# power.net
KiCad netlist of a schematic drawn in Altium Designer
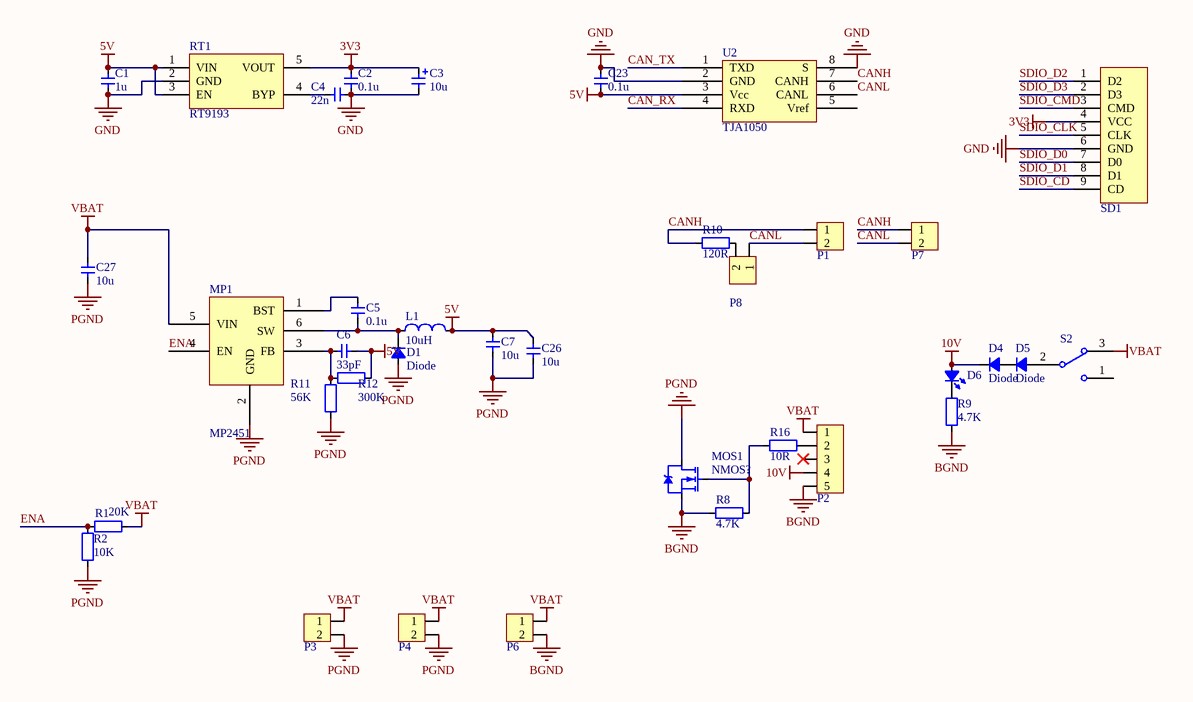
[diagram p0: power.SchDoc]

(export (version "E")
  (design (tool "Eeschema 10.0.6"))
  (components
    (comp (ref "C1")
      (value "1u")
      (footprint "PCB_PassiveCap:CAP_0603")
      (description "Capacitor")
      (fields (field (name "Comment") "Cap_0603"))
      (libsource (lib "SCH_Passive") (part "Cap_0603"))
    )
    (comp (ref "C2")
      (value "0.1u")
      (footprint "PCB_PassiveCap:CAP_0603")
      (description "Capacitor")
      (fields (field (name "Comment") "Cap_0603"))
      (libsource (lib "SCH_Passive") (part "Cap_0603"))
    )
    (comp (ref "C3")
      (value "10u")
      (footprint "PCB_PassiveCap:CAP_TAN_P0805")
      (description "Capacitor")
      (fields (field (name "Comment") "Cap_Tan_0805"))
      (libsource (lib "SCH_Passive") (part "Cap_Tan_0805"))
    )
    (comp (ref "C4")
      (value "22n")
      (footprint "PCB_PassiveCap:CAP_0603")
      (description "Capacitor")
      (fields (field (name "Comment") "Cap_0603"))
      (libsource (lib "SCH_Passive") (part "Cap_0603"))
    )
    (comp (ref "C5")
      (value "0.1u")
      (footprint "PCB_PassiveCap:CAP_0603")
      (description "Capacitor")
      (fields (field (name "Comment") "Cap_0603"))
      (libsource (lib "SCH_Passive") (part "Cap_0603"))
    )
    (comp (ref "C6")
      (value "33pF")
      (footprint "PCB_PassiveCap:CAP_0603")
      (description "Capacitor")
      (fields (field (name "Comment") "Cap_0603"))
      (libsource (lib "SCH_Passive") (part "Cap_0603"))
    )
    (comp (ref "C7")
      (value "10u")
      (footprint "PCB_PassiveCap:CAP_0805")
      (description "Capacitor")
      (fields (field (name "Comment") "Cap_0805"))
      (libsource (lib "SCH_Passive") (part "Cap_0805"))
    )
    (comp (ref "C23")
      (value "0.1u")
      (footprint "PCB_PassiveCap:CAP_0603")
      (description "Capacitor")
      (fields (field (name "Comment") "Cap_0603"))
      (libsource (lib "SCH_Passive") (part "Cap_0603"))
    )
    (comp (ref "C26")
      (value "10u")
      (footprint "PCB_PassiveCap:CAP_0805")
      (description "Capacitor")
      (fields (field (name "Comment") "Cap_0805"))
      (libsource (lib "SCH_Passive") (part "Cap_0805"))
    )
    (comp (ref "C27")
      (value "10u")
      (footprint "PCB_PassiveCap:CAP_0805")
      (description "Capacitor")
      (fields (field (name "Comment") "Cap_0805"))
      (libsource (lib "SCH_Passive") (part "Cap_0805"))
    )
    (comp (ref "D1") (value "Diode") (footprint "LED_0805_RED") (libsource (lib "SCH_Active") (part "Diode")))
    (comp (ref "D4") (value "Diode") (footprint "LED_0805_RED") (libsource (lib "SCH_Active") (part "Diode")))
    (comp (ref "D5") (value "Diode") (footprint "LED_0805_RED") (libsource (lib "SCH_Active") (part "Diode")))
    (comp (ref "D6")
      (value "LED_0805")
      (footprint "PCB_ActiveLED:LED_0805_RED")
      (description "LED")
      (libsource (lib "SCH_Active") (part "LED_0805"))
    )
    (comp (ref "L1")
      (value "10uH")
      (footprint "IND_CD52")
      (description "Inductor")
      (fields (field (name "Comment") "Ind_CD32"))
      (libsource (lib "SCH_Passive") (part "Ind_CD32"))
    )
    (comp (ref "MOS1")
      (value "NMOS?")
      (footprint "PCB_IntegratedCircuit:TO-252AA")
      (description "MOSFET")
      (fields (field (name "Comment") "MOSFET_N"))
      (libsource (lib "SCH_Active") (part "MOSFET_N"))
    )
    (comp (ref "MP1")
      (value "MP2451")
      (footprint "SOT23-6")
      (libsource (lib "SCH_IntegratedCircuit") (part "MP2451"))
    )
    (comp (ref "P1")
      (value "HDR1x2_2.54")
      (footprint "PCB_ConnectorHDR:HDR1X2_2.54_90")
      (description "Header")
      (libsource (lib "") (part "HDR1x2_2.54_1"))
    )
    (comp (ref "P2")
      (value "HDR1x5_2.54")
      (footprint "PCB_ConnectorHDR:HDR1X5_2.54_180")
      (description "Header")
      (libsource (lib "SCH_ConnectorHDR") (part "HDR1x5_2.54"))
    )
    (comp (ref "P3")
      (value "Connector")
      (footprint "XT30_PW_M")
      (libsource (lib "SCH_Connector") (part "2P"))
    )
    (comp (ref "P4")
      (value "Connector")
      (footprint "XT30_PW_M")
      (libsource (lib "SCH_Connector") (part "2P"))
    )
    (comp (ref "P6")
      (value "Connector")
      (footprint "XT30_PW_M")
      (libsource (lib "SCH_Connector") (part "2P"))
    )
    (comp (ref "P7")
      (value "HDR1x2_2.54")
      (footprint "PCB_ConnectorHDR:HDR1X2_2.54_90")
      (description "Header")
      (libsource (lib "") (part "HDR1x2_2.54_1"))
    )
    (comp (ref "P8")
      (value "HDR1x2_2.54")
      (footprint "PCB_ConnectorHDR:HDR1X2_2.54_180")
      (description "Header")
      (libsource (lib "SCH_ConnectorHDR") (part "HDR1x2_2.54"))
    )
    (comp (ref "R1")
      (value "20K")
      (footprint "PCB_PassiveRes:RES_0603")
      (description "Resistor")
      (fields (field (name "Comment") "Res_0603"))
      (libsource (lib "") (part "Res_0603_1"))
    )
    (comp (ref "R2")
      (value "10K")
      (footprint "PCB_PassiveRes:RES_0603")
      (description "Resistor")
      (fields (field (name "Comment") "Res_0603"))
      (libsource (lib "") (part "Res_0603_2"))
    )
    (comp (ref "R8")
      (value "4.7K")
      (footprint "PCB_PassiveRes:RES_0603")
      (description "Resistor")
      (fields (field (name "Comment") "Res_0603"))
      (libsource (lib "SCH_Passive") (part "Res_0603"))
    )
    (comp (ref "R9")
      (value "4.7K")
      (footprint "PCB_PassiveRes:RES_0603")
      (description "Resistor")
      (fields (field (name "Comment") "Res_0603"))
      (libsource (lib "") (part "Res_0603_3"))
    )
    (comp (ref "R10")
      (value "120R")
      (footprint "PCB_PassiveRes:RES_0603")
      (description "Resistor")
      (fields (field (name "Comment") "Res_0603"))
      (libsource (lib "SCH_Passive") (part "Res_0603"))
    )
    (comp (ref "R11")
      (value "56K")
      (footprint "PCB_PassiveRes:RES_0603")
      (description "Resistor")
      (fields (field (name "Comment") "Res_0603"))
      (libsource (lib "") (part "Res_0603_2"))
    )
    (comp (ref "R12")
      (value "300K")
      (footprint "PCB_PassiveRes:RES_0603")
      (description "Resistor")
      (fields (field (name "Comment") "Res_0603"))
      (libsource (lib "") (part "Res_0603_1"))
    )
    (comp (ref "R16")
      (value "10R")
      (footprint "PCB_PassiveRes:RES_0603")
      (description "Resistor")
      (fields (field (name "Comment") "Res_0603"))
      (libsource (lib "SCH_Passive") (part "Res_0603"))
    )
    (comp (ref "RT1")
      (value "RT9193")
      (footprint "PCB_IntegratedCircuit:SOT23-5")
      (description "Power")
      (libsource (lib "SCH_IntegratedCircuit") (part "RT9193"))
    )
    (comp (ref "S2")
      (value "SwitchSPDT_2.8x6.6_90")
      (footprint "PCB_Switch:SwitchSPDT_2.8X6.6_90")
      (description "Switch")
      (libsource (lib "SCH_Switch") (part "SwitchSPDT_2.8x6.6_90"))
    )
    (comp (ref "SD1")
      (value "SD_Card_TF")
      (footprint "PCB_SDCard:SD_Card_TF")
      (description "SD")
      (libsource (lib "SCH_SDCard") (part "SD_Card_TF"))
    )
    (comp (ref "U2")
      (value "TJA1050")
      (footprint "SOP_E150_8")
      (libsource (lib "SCH_IntegratedCircuit") (part "TJA1050"))
    )
  )
  (nets
    (net (code "1") (name "/CANH") (class "Default")
      (node (ref "P1") (pin "1") (pinfunction "1_1") (pintype "passive"))
      (node (ref "P7") (pin "1") (pinfunction "1_1") (pintype "passive"))
      (node (ref "R10") (pin "2") (pinfunction "2_2") (pintype "passive"))
      (node (ref "U2") (pin "7") (pinfunction "CANH_7") (pintype "passive"))
    )
    (net (code "2") (name "/CANL") (class "Default")
      (node (ref "P1") (pin "2") (pinfunction "2_2") (pintype "passive"))
      (node (ref "P7") (pin "2") (pinfunction "2_2") (pintype "passive"))
      (node (ref "P8") (pin "1") (pinfunction "1_1") (pintype "passive"))
      (node (ref "U2") (pin "6") (pinfunction "CANL_6") (pintype "passive"))
    )
    (net (code "3") (name "/CAN_RX") (class "Default")
      (node (ref "U2") (pin "4") (pinfunction "RXD_4") (pintype "passive"))
    )
    (net (code "4") (name "/CAN_TX") (class "Default")
      (node (ref "U2") (pin "1") (pinfunction "TXD_1") (pintype "passive"))
    )
    (net (code "5") (name "/ENA") (class "Default")
      (node (ref "MP1") (pin "4") (pinfunction "EN_4") (pintype "passive"))
      (node (ref "R1") (pin "1") (pinfunction "1_1") (pintype "passive"))
      (node (ref "R2") (pin "1") (pinfunction "1_1") (pintype "passive"))
    )
    (net (code "6") (name "/SDIO_CD") (class "Default")
      (node (ref "SD1") (pin "9") (pinfunction "CD_9") (pintype "passive"))
    )
    (net (code "7") (name "/SDIO_CLK") (class "Default")
      (node (ref "SD1") (pin "5") (pinfunction "CLK_5") (pintype "passive"))
    )
    (net (code "8") (name "/SDIO_CMD") (class "Default")
      (node (ref "SD1") (pin "3") (pinfunction "CMD_3") (pintype "passive"))
    )
    (net (code "9") (name "/SDIO_D0") (class "Default")
      (node (ref "SD1") (pin "7") (pinfunction "D0_7") (pintype "passive"))
    )
    (net (code "10") (name "/SDIO_D1") (class "Default")
      (node (ref "SD1") (pin "8") (pinfunction "D1_8") (pintype "passive"))
    )
    (net (code "11") (name "/SDIO_D2") (class "Default")
      (node (ref "SD1") (pin "1") (pinfunction "D2_1") (pintype "passive"))
    )
    (net (code "12") (name "/SDIO_D3") (class "Default")
      (node (ref "SD1") (pin "2") (pinfunction "D3_2") (pintype "passive"))
    )
    (net (code "13") (name "3V3") (class "Default")
      (node (ref "C2") (pin "2") (pinfunction "2_2") (pintype "passive"))
      (node (ref "C3") (pin "1") (pinfunction "1_1") (pintype "passive"))
      (node (ref "RT1") (pin "5") (pinfunction "VOUT_5") (pintype "passive"))
      (node (ref "SD1") (pin "4") (pinfunction "VCC_4") (pintype "passive"))
    )
    (net (code "14") (name "5V") (class "Default")
      (node (ref "C1") (pin "2") (pinfunction "2_2") (pintype "passive"))
      (node (ref "C23") (pin "1") (pinfunction "1_1") (pintype "passive"))
      (node (ref "C26") (pin "2") (pinfunction "2_2") (pintype "passive"))
      (node (ref "C6") (pin "1") (pinfunction "1_1") (pintype "passive"))
      (node (ref "C7") (pin "2") (pinfunction "2_2") (pintype "passive"))
      (node (ref "L1") (pin "2") (pinfunction "2_2") (pintype "passive"))
      (node (ref "R12") (pin "2") (pinfunction "2_2") (pintype "passive"))
      (node (ref "RT1") (pin "1") (pinfunction "VIN_1") (pintype "passive"))
      (node (ref "RT1") (pin "3") (pinfunction "EN_3") (pintype "power_in"))
      (node (ref "U2") (pin "3") (pinfunction "Vcc_3") (pintype "passive"))
    )
    (net (code "15") (name "10V") (class "Default")
      (node (ref "D4") (pin "2") (pinfunction "K_2") (pintype "passive"))
      (node (ref "D6") (pin "1") (pinfunction "A_1") (pintype "passive"))
      (node (ref "P2") (pin "4") (pinfunction "4_4") (pintype "passive"))
    )
    (net (code "16") (name "BGND") (class "Default")
      (node (ref "MOS1") (pin "3") (pinfunction "S_3") (pintype "passive"))
      (node (ref "P2") (pin "5") (pinfunction "5_5") (pintype "passive"))
      (node (ref "P6") (pin "2") (pinfunction "2_2") (pintype "passive"))
      (node (ref "R8") (pin "2") (pinfunction "2_2") (pintype "passive"))
      (node (ref "R9") (pin "1") (pinfunction "1_1") (pintype "passive"))
    )
    (net (code "17") (name "GND") (class "Default")
      (node (ref "C1") (pin "1") (pinfunction "1_1") (pintype "passive"))
      (node (ref "C2") (pin "1") (pinfunction "1_1") (pintype "passive"))
      (node (ref "C23") (pin "2") (pinfunction "2_2") (pintype "passive"))
      (node (ref "C3") (pin "2") (pinfunction "2_2") (pintype "passive"))
      (node (ref "C4") (pin "1") (pinfunction "1_1") (pintype "passive"))
      (node (ref "RT1") (pin "2") (pinfunction "GND_2") (pintype "passive"))
      (node (ref "SD1") (pin "6") (pinfunction "GND_6") (pintype "passive"))
      (node (ref "U2") (pin "2") (pinfunction "GND_2") (pintype "passive"))
      (node (ref "U2") (pin "8") (pinfunction "S_8") (pintype "passive"))
    )
    (net (code "18") (name "Net-(D1-K)") (class "Default")
      (node (ref "C5") (pin "1") (pinfunction "1_1") (pintype "passive"))
      (node (ref "D1") (pin "2") (pinfunction "K_2") (pintype "passive"))
      (node (ref "L1") (pin "1") (pinfunction "1_1") (pintype "passive"))
      (node (ref "MP1") (pin "6") (pinfunction "SW_6") (pintype "passive"))
    )
    (net (code "19") (name "Net-(D4-A)") (class "Default")
      (node (ref "D4") (pin "1") (pinfunction "A_1") (pintype "passive"))
      (node (ref "D5") (pin "2") (pinfunction "K_2") (pintype "passive"))
    )
    (net (code "20") (name "Net-(D5-A)") (class "Default")
      (node (ref "D5") (pin "1") (pinfunction "A_1") (pintype "passive"))
      (node (ref "S2") (pin "2") (pinfunction "2_2") (pintype "passive"))
    )
    (net (code "21") (name "Net-(D6-K)") (class "Default")
      (node (ref "D6") (pin "2") (pinfunction "K_2") (pintype "passive"))
      (node (ref "R9") (pin "2") (pinfunction "2_2") (pintype "passive"))
    )
    (net (code "22") (name "Net-(MOS1-G)") (class "Default")
      (node (ref "MOS1") (pin "1") (pinfunction "G_1") (pintype "passive"))
      (node (ref "R16") (pin "2") (pinfunction "2_2") (pintype "passive"))
      (node (ref "R8") (pin "1") (pinfunction "1_1") (pintype "passive"))
    )
    (net (code "23") (name "Net-(MP1-BST)") (class "Default")
      (node (ref "C5") (pin "2") (pinfunction "2_2") (pintype "passive"))
      (node (ref "MP1") (pin "1") (pinfunction "BST_1") (pintype "passive"))
    )
    (net (code "24") (name "Net-(MP1-FB)") (class "Default")
      (node (ref "C6") (pin "2") (pinfunction "2_2") (pintype "passive"))
      (node (ref "MP1") (pin "3") (pinfunction "FB_3") (pintype "passive"))
      (node (ref "R11") (pin "1") (pinfunction "1_1") (pintype "passive"))
      (node (ref "R12") (pin "1") (pinfunction "1_1") (pintype "passive"))
    )
    (net (code "25") (name "Net-(P2-Pad2)") (class "Default")
      (node (ref "P2") (pin "2") (pinfunction "2_2") (pintype "passive"))
      (node (ref "R16") (pin "1") (pinfunction "1_1") (pintype "passive"))
    )
    (net (code "26") (name "Net-(P8-Pad2)") (class "Default")
      (node (ref "P8") (pin "2") (pinfunction "2_2") (pintype "passive"))
      (node (ref "R10") (pin "1") (pinfunction "1_1") (pintype "passive"))
    )
    (net (code "27") (name "Net-(RT1-BYP)") (class "Default")
      (node (ref "C4") (pin "2") (pinfunction "2_2") (pintype "passive"))
      (node (ref "RT1") (pin "4") (pinfunction "BYP_4") (pintype "passive"))
    )
    (net (code "28") (name "PGND") (class "Default")
      (node (ref "C26") (pin "1") (pinfunction "1_1") (pintype "passive"))
      (node (ref "C27") (pin "1") (pinfunction "1_1") (pintype "passive"))
      (node (ref "C7") (pin "1") (pinfunction "1_1") (pintype "passive"))
      (node (ref "D1") (pin "1") (pinfunction "A_1") (pintype "passive"))
      (node (ref "MOS1") (pin "4") (pinfunction "D_4") (pintype "passive"))
      (node (ref "MP1") (pin "2") (pinfunction "GND_2") (pintype "passive"))
      (node (ref "P3") (pin "2") (pinfunction "2_2") (pintype "passive"))
      (node (ref "P4") (pin "2") (pinfunction "2_2") (pintype "passive"))
      (node (ref "R11") (pin "2") (pinfunction "2_2") (pintype "passive"))
      (node (ref "R2") (pin "2") (pinfunction "2_2") (pintype "passive"))
    )
    (net (code "29") (name "VBAT") (class "Default")
      (node (ref "C27") (pin "2") (pinfunction "2_2") (pintype "passive"))
      (node (ref "MP1") (pin "5") (pinfunction "VIN_5") (pintype "passive"))
      (node (ref "P2") (pin "1") (pinfunction "1_1") (pintype "passive"))
      (node (ref "P3") (pin "1") (pinfunction "1_1") (pintype "passive"))
      (node (ref "P4") (pin "1") (pinfunction "1_1") (pintype "passive"))
      (node (ref "P6") (pin "1") (pinfunction "1_1") (pintype "passive"))
      (node (ref "R1") (pin "2") (pinfunction "2_2") (pintype "passive"))
      (node (ref "S2") (pin "3") (pinfunction "3_3") (pintype "passive"))
    )
    (net (code "30") (name "unconnected-(P2-Pad3)") (class "Default")
      (node (ref "P2") (pin "3") (pinfunction "3_3") (pintype "passive+no_connect"))
    )
    (net (code "31") (name "unconnected-(S2-Pad1)") (class "Default")
      (node (ref "S2") (pin "1") (pinfunction "1_1") (pintype "passive"))
    )
    (net (code "32") (name "unconnected-(U2-Vref-Pad5)") (class "Default")
      (node (ref "U2") (pin "5") (pinfunction "Vref_5") (pintype "passive"))
    )
  )
)
